# 3_-_Drivers.net
KiCad netlist of a schematic drawn in Altium Designer
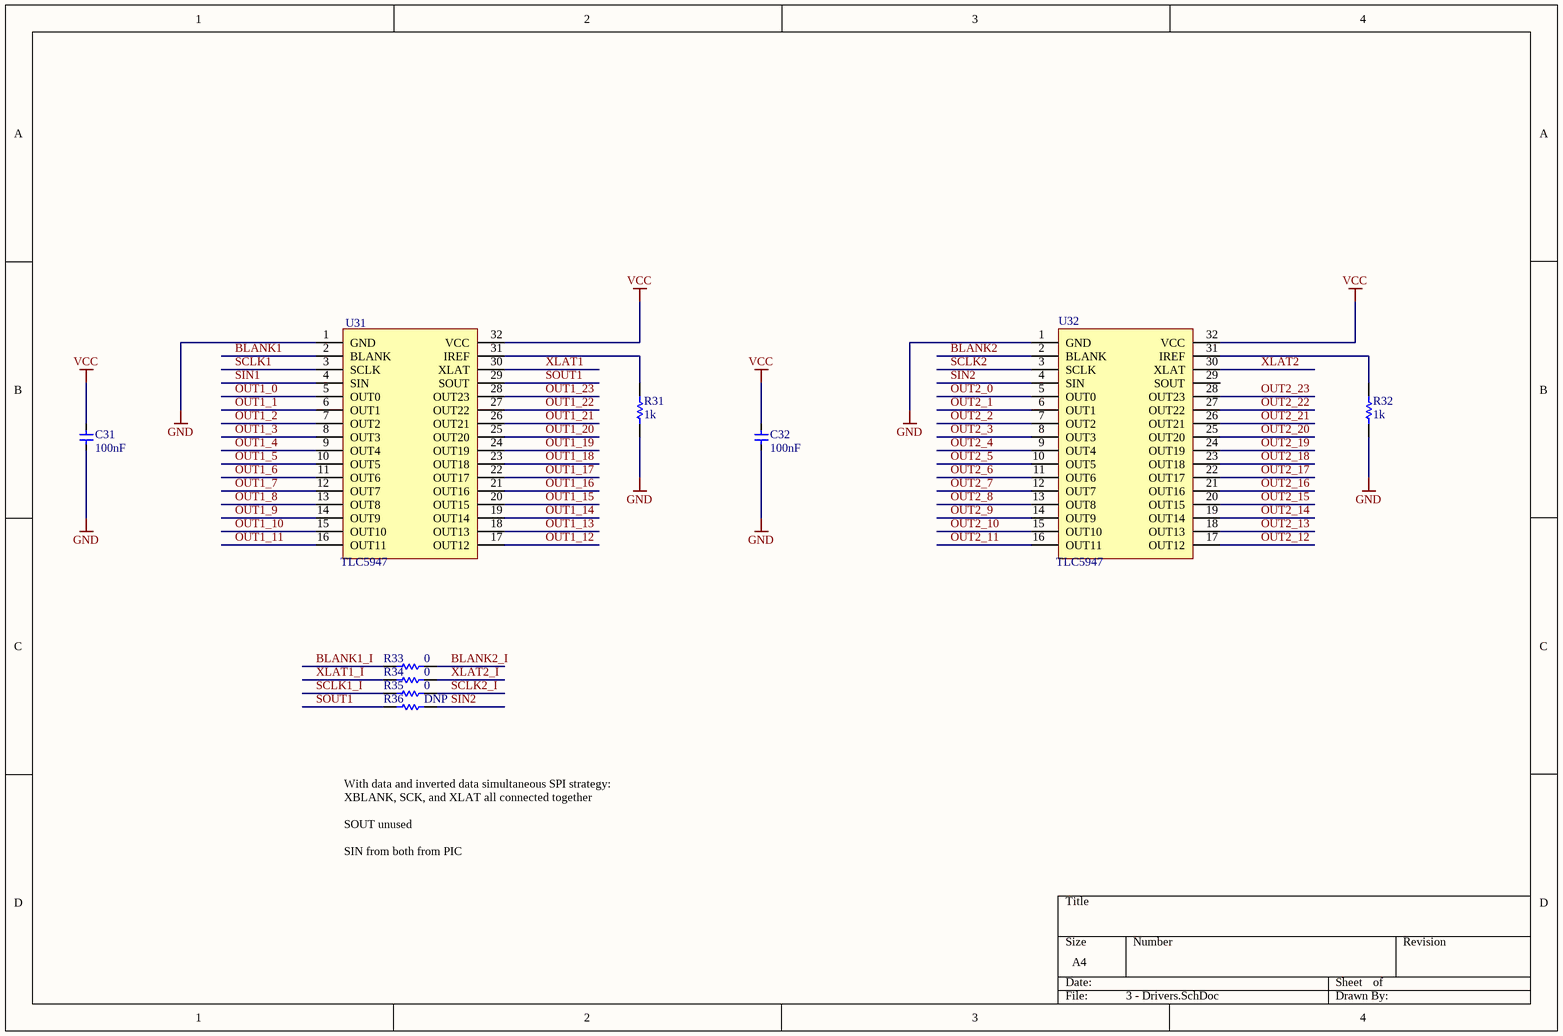
[diagram p0: 3 - Drivers.SchDoc]

(export (version "E")
  (design (tool "Eeschema 10.0.6"))
  (components
    (comp (ref "C31")
      (value "100nF")
      (footprint "PCB_PassiveCap:CAP_0603")
      (description "Capacitor")
      (fields (field (name "Comment") "Cap_0603"))
      (libsource (lib "SCH_Passive") (part "Cap_0603"))
    )
    (comp (ref "C32")
      (value "100nF")
      (footprint "PCB_PassiveCap:CAP_0603")
      (description "Capacitor")
      (fields (field (name "Comment") "Cap_0603"))
      (libsource (lib "SCH_Passive") (part "Cap_0603"))
    )
    (comp (ref "R31")
      (value "1k")
      (footprint "RES_0603")
      (description "Resistor")
      (fields (field (name "Comment") "Res1") (field (name "PUBLISHER") "Altium Limited"))
      (libsource (lib "Miscellaneous Devices") (part "Res1"))
    )
    (comp (ref "R32")
      (value "1k")
      (footprint "RES_0603")
      (description "Resistor")
      (fields (field (name "Comment") "Res1") (field (name "PUBLISHER") "Altium Limited"))
      (libsource (lib "Miscellaneous Devices") (part "Res1"))
    )
    (comp (ref "R33")
      (value "0")
      (footprint "RES_0603")
      (description "Resistor")
      (fields (field (name "Comment") "Res1") (field (name "PUBLISHER") "Altium Limited"))
      (libsource (lib "Miscellaneous Devices") (part "Res1"))
    )
    (comp (ref "R34")
      (value "0")
      (footprint "RES_0603")
      (description "Resistor")
      (fields (field (name "Comment") "Res1") (field (name "PUBLISHER") "Altium Limited"))
      (libsource (lib "Miscellaneous Devices") (part "Res1"))
    )
    (comp (ref "R35")
      (value "0")
      (footprint "RES_0603")
      (description "Resistor")
      (fields (field (name "Comment") "Res1") (field (name "PUBLISHER") "Altium Limited"))
      (libsource (lib "Miscellaneous Devices") (part "Res1"))
    )
    (comp (ref "R36")
      (value "DNP")
      (footprint "RES_0603")
      (description "Resistor")
      (fields (field (name "Comment") "Res1") (field (name "PUBLISHER") "Altium Limited"))
      (libsource (lib "Miscellaneous Devices") (part "Res1"))
    )
    (comp (ref "U31")
      (value "TLC5947")
      (footprint "QFN50P500X500X100-33N")
      (description "LED Driver")
      (libsource (lib "SCH_IntegratedCircuit") (part "TLC5947"))
    )
    (comp (ref "U32")
      (value "TLC5947")
      (footprint "QFN50P500X500X100-33N")
      (description "LED Driver")
      (libsource (lib "SCH_IntegratedCircuit") (part "TLC5947"))
    )
  )
  (nets
    (net (code "1") (name "/BLANK1") (class "Default")
      (node (ref "U31") (pin "2") (pinfunction "BLANK_2") (pintype "passive"))
    )
    (net (code "2") (name "/BLANK1_I") (class "Default")
      (node (ref "R33") (pin "2") (pinfunction "2_2") (pintype "passive"))
    )
    (net (code "3") (name "/BLANK2") (class "Default")
      (node (ref "U32") (pin "2") (pinfunction "BLANK_2") (pintype "passive"))
    )
    (net (code "4") (name "/BLANK2_I") (class "Default")
      (node (ref "R33") (pin "1") (pinfunction "1_1") (pintype "passive"))
    )
    (net (code "5") (name "/OUT1_0") (class "Default")
      (node (ref "U31") (pin "5") (pinfunction "OUT0_5") (pintype "passive"))
    )
    (net (code "6") (name "/OUT1_1") (class "Default")
      (node (ref "U31") (pin "6") (pinfunction "OUT1_6") (pintype "passive"))
    )
    (net (code "7") (name "/OUT1_2") (class "Default")
      (node (ref "U31") (pin "7") (pinfunction "OUT2_7") (pintype "passive"))
    )
    (net (code "8") (name "/OUT1_3") (class "Default")
      (node (ref "U31") (pin "8") (pinfunction "OUT3_8") (pintype "passive"))
    )
    (net (code "9") (name "/OUT1_4") (class "Default")
      (node (ref "U31") (pin "9") (pinfunction "OUT4_9") (pintype "passive"))
    )
    (net (code "10") (name "/OUT1_5") (class "Default")
      (node (ref "U31") (pin "10") (pinfunction "OUT5_10") (pintype "passive"))
    )
    (net (code "11") (name "/OUT1_6") (class "Default")
      (node (ref "U31") (pin "11") (pinfunction "OUT6_11") (pintype "passive"))
    )
    (net (code "12") (name "/OUT1_7") (class "Default")
      (node (ref "U31") (pin "12") (pinfunction "OUT7_12") (pintype "passive"))
    )
    (net (code "13") (name "/OUT1_8") (class "Default")
      (node (ref "U31") (pin "13") (pinfunction "OUT8_13") (pintype "passive"))
    )
    (net (code "14") (name "/OUT1_9") (class "Default")
      (node (ref "U31") (pin "14") (pinfunction "OUT9_14") (pintype "passive"))
    )
    (net (code "15") (name "/OUT1_10") (class "Default")
      (node (ref "U31") (pin "15") (pinfunction "OUT10_15") (pintype "passive"))
    )
    (net (code "16") (name "/OUT1_11") (class "Default")
      (node (ref "U31") (pin "16") (pinfunction "OUT11_16") (pintype "passive"))
    )
    (net (code "17") (name "/OUT1_12") (class "Default")
      (node (ref "U31") (pin "17") (pinfunction "OUT12_17") (pintype "passive"))
    )
    (net (code "18") (name "/OUT1_13") (class "Default")
      (node (ref "U31") (pin "18") (pinfunction "OUT13_18") (pintype "passive"))
    )
    (net (code "19") (name "/OUT1_14") (class "Default")
      (node (ref "U31") (pin "19") (pinfunction "OUT14_19") (pintype "passive"))
    )
    (net (code "20") (name "/OUT1_15") (class "Default")
      (node (ref "U31") (pin "20") (pinfunction "OUT15_20") (pintype "passive"))
    )
    (net (code "21") (name "/OUT1_16") (class "Default")
      (node (ref "U31") (pin "21") (pinfunction "OUT16_21") (pintype "passive"))
    )
    (net (code "22") (name "/OUT1_17") (class "Default")
      (node (ref "U31") (pin "22") (pinfunction "OUT17_22") (pintype "passive"))
    )
    (net (code "23") (name "/OUT1_18") (class "Default")
      (node (ref "U31") (pin "23") (pinfunction "OUT18_23") (pintype "passive"))
    )
    (net (code "24") (name "/OUT1_19") (class "Default")
      (node (ref "U31") (pin "24") (pinfunction "OUT19_24") (pintype "passive"))
    )
    (net (code "25") (name "/OUT1_20") (class "Default")
      (node (ref "U31") (pin "25") (pinfunction "OUT20_25") (pintype "passive"))
    )
    (net (code "26") (name "/OUT1_21") (class "Default")
      (node (ref "U31") (pin "26") (pinfunction "OUT21_26") (pintype "passive"))
    )
    (net (code "27") (name "/OUT1_22") (class "Default")
      (node (ref "U31") (pin "27") (pinfunction "OUT22_27") (pintype "passive"))
    )
    (net (code "28") (name "/OUT1_23") (class "Default")
      (node (ref "U31") (pin "28") (pinfunction "OUT23_28") (pintype "passive"))
    )
    (net (code "29") (name "/OUT2_0") (class "Default")
      (node (ref "U32") (pin "5") (pinfunction "OUT0_5") (pintype "passive"))
    )
    (net (code "30") (name "/OUT2_1") (class "Default")
      (node (ref "U32") (pin "6") (pinfunction "OUT1_6") (pintype "passive"))
    )
    (net (code "31") (name "/OUT2_2") (class "Default")
      (node (ref "U32") (pin "7") (pinfunction "OUT2_7") (pintype "passive"))
    )
    (net (code "32") (name "/OUT2_3") (class "Default")
      (node (ref "U32") (pin "8") (pinfunction "OUT3_8") (pintype "passive"))
    )
    (net (code "33") (name "/OUT2_4") (class "Default")
      (node (ref "U32") (pin "9") (pinfunction "OUT4_9") (pintype "passive"))
    )
    (net (code "34") (name "/OUT2_5") (class "Default")
      (node (ref "U32") (pin "10") (pinfunction "OUT5_10") (pintype "passive"))
    )
    (net (code "35") (name "/OUT2_6") (class "Default")
      (node (ref "U32") (pin "11") (pinfunction "OUT6_11") (pintype "passive"))
    )
    (net (code "36") (name "/OUT2_7") (class "Default")
      (node (ref "U32") (pin "12") (pinfunction "OUT7_12") (pintype "passive"))
    )
    (net (code "37") (name "/OUT2_8") (class "Default")
      (node (ref "U32") (pin "13") (pinfunction "OUT8_13") (pintype "passive"))
    )
    (net (code "38") (name "/OUT2_9") (class "Default")
      (node (ref "U32") (pin "14") (pinfunction "OUT9_14") (pintype "passive"))
    )
    (net (code "39") (name "/OUT2_10") (class "Default")
      (node (ref "U32") (pin "15") (pinfunction "OUT10_15") (pintype "passive"))
    )
    (net (code "40") (name "/OUT2_11") (class "Default")
      (node (ref "U32") (pin "16") (pinfunction "OUT11_16") (pintype "passive"))
    )
    (net (code "41") (name "/OUT2_12") (class "Default")
      (node (ref "U32") (pin "17") (pinfunction "OUT12_17") (pintype "passive"))
    )
    (net (code "42") (name "/OUT2_13") (class "Default")
      (node (ref "U32") (pin "18") (pinfunction "OUT13_18") (pintype "passive"))
    )
    (net (code "43") (name "/OUT2_14") (class "Default")
      (node (ref "U32") (pin "19") (pinfunction "OUT14_19") (pintype "passive"))
    )
    (net (code "44") (name "/OUT2_15") (class "Default")
      (node (ref "U32") (pin "20") (pinfunction "OUT15_20") (pintype "passive"))
    )
    (net (code "45") (name "/OUT2_16") (class "Default")
      (node (ref "U32") (pin "21") (pinfunction "OUT16_21") (pintype "passive"))
    )
    (net (code "46") (name "/OUT2_17") (class "Default")
      (node (ref "U32") (pin "22") (pinfunction "OUT17_22") (pintype "passive"))
    )
    (net (code "47") (name "/OUT2_18") (class "Default")
      (node (ref "U32") (pin "23") (pinfunction "OUT18_23") (pintype "passive"))
    )
    (net (code "48") (name "/OUT2_19") (class "Default")
      (node (ref "U32") (pin "24") (pinfunction "OUT19_24") (pintype "passive"))
    )
    (net (code "49") (name "/OUT2_20") (class "Default")
      (node (ref "U32") (pin "25") (pinfunction "OUT20_25") (pintype "passive"))
    )
    (net (code "50") (name "/OUT2_21") (class "Default")
      (node (ref "U32") (pin "26") (pinfunction "OUT21_26") (pintype "passive"))
    )
    (net (code "51") (name "/OUT2_22") (class "Default")
      (node (ref "U32") (pin "27") (pinfunction "OUT22_27") (pintype "passive"))
    )
    (net (code "52") (name "/OUT2_23") (class "Default")
      (node (ref "U32") (pin "28") (pinfunction "OUT23_28") (pintype "passive"))
    )
    (net (code "53") (name "/SCLK1") (class "Default")
      (node (ref "U31") (pin "3") (pinfunction "SCLK_3") (pintype "passive"))
    )
    (net (code "54") (name "/SCLK1_I") (class "Default")
      (node (ref "R35") (pin "2") (pinfunction "2_2") (pintype "passive"))
    )
    (net (code "55") (name "/SCLK2") (class "Default")
      (node (ref "U32") (pin "3") (pinfunction "SCLK_3") (pintype "passive"))
    )
    (net (code "56") (name "/SCLK2_I") (class "Default")
      (node (ref "R35") (pin "1") (pinfunction "1_1") (pintype "passive"))
    )
    (net (code "57") (name "/SIN1") (class "Default")
      (node (ref "U31") (pin "4") (pinfunction "SIN_4") (pintype "passive"))
    )
    (net (code "58") (name "/SIN2") (class "Default")
      (node (ref "R36") (pin "1") (pinfunction "1_1") (pintype "passive"))
      (node (ref "U32") (pin "4") (pinfunction "SIN_4") (pintype "passive"))
    )
    (net (code "59") (name "/SOUT1") (class "Default")
      (node (ref "R36") (pin "2") (pinfunction "2_2") (pintype "passive"))
      (node (ref "U31") (pin "29") (pinfunction "SOUT_29") (pintype "passive"))
    )
    (net (code "60") (name "/XLAT1") (class "Default")
      (node (ref "U31") (pin "30") (pinfunction "XLAT_30") (pintype "passive"))
    )
    (net (code "61") (name "/XLAT1_I") (class "Default")
      (node (ref "R34") (pin "2") (pinfunction "2_2") (pintype "passive"))
    )
    (net (code "62") (name "/XLAT2") (class "Default")
      (node (ref "U32") (pin "30") (pinfunction "XLAT_30") (pintype "passive"))
    )
    (net (code "63") (name "/XLAT2_I") (class "Default")
      (node (ref "R34") (pin "1") (pinfunction "1_1") (pintype "passive"))
    )
    (net (code "64") (name "GND") (class "Default")
      (node (ref "C31") (pin "1") (pinfunction "1_1") (pintype "passive"))
      (node (ref "C32") (pin "1") (pinfunction "1_1") (pintype "passive"))
      (node (ref "R31") (pin "1") (pinfunction "1_1") (pintype "passive"))
      (node (ref "R32") (pin "1") (pinfunction "1_1") (pintype "passive"))
      (node (ref "U31") (pin "1") (pinfunction "GND_1") (pintype "passive"))
      (node (ref "U32") (pin "1") (pinfunction "GND_1") (pintype "passive"))
    )
    (net (code "65") (name "Net-(U31-IREF)") (class "Default")
      (node (ref "R31") (pin "2") (pinfunction "2_2") (pintype "passive"))
      (node (ref "U31") (pin "31") (pinfunction "IREF_31") (pintype "passive"))
    )
    (net (code "66") (name "Net-(U32-IREF)") (class "Default")
      (node (ref "R32") (pin "2") (pinfunction "2_2") (pintype "passive"))
      (node (ref "U32") (pin "31") (pinfunction "IREF_31") (pintype "passive"))
    )
    (net (code "67") (name "VCC") (class "Default")
      (node (ref "C31") (pin "2") (pinfunction "2_2") (pintype "passive"))
      (node (ref "C32") (pin "2") (pinfunction "2_2") (pintype "passive"))
      (node (ref "U31") (pin "32") (pinfunction "VCC_32") (pintype "passive"))
      (node (ref "U32") (pin "32") (pinfunction "VCC_32") (pintype "passive"))
    )
    (net (code "68") (name "unconnected-(U32-SOUT-Pad29)") (class "Default")
      (node (ref "U32") (pin "29") (pinfunction "SOUT_29") (pintype "passive"))
    )
  )
)
